# STM32_MCU.net
KiCad netlist of a schematic drawn in Altium Designer
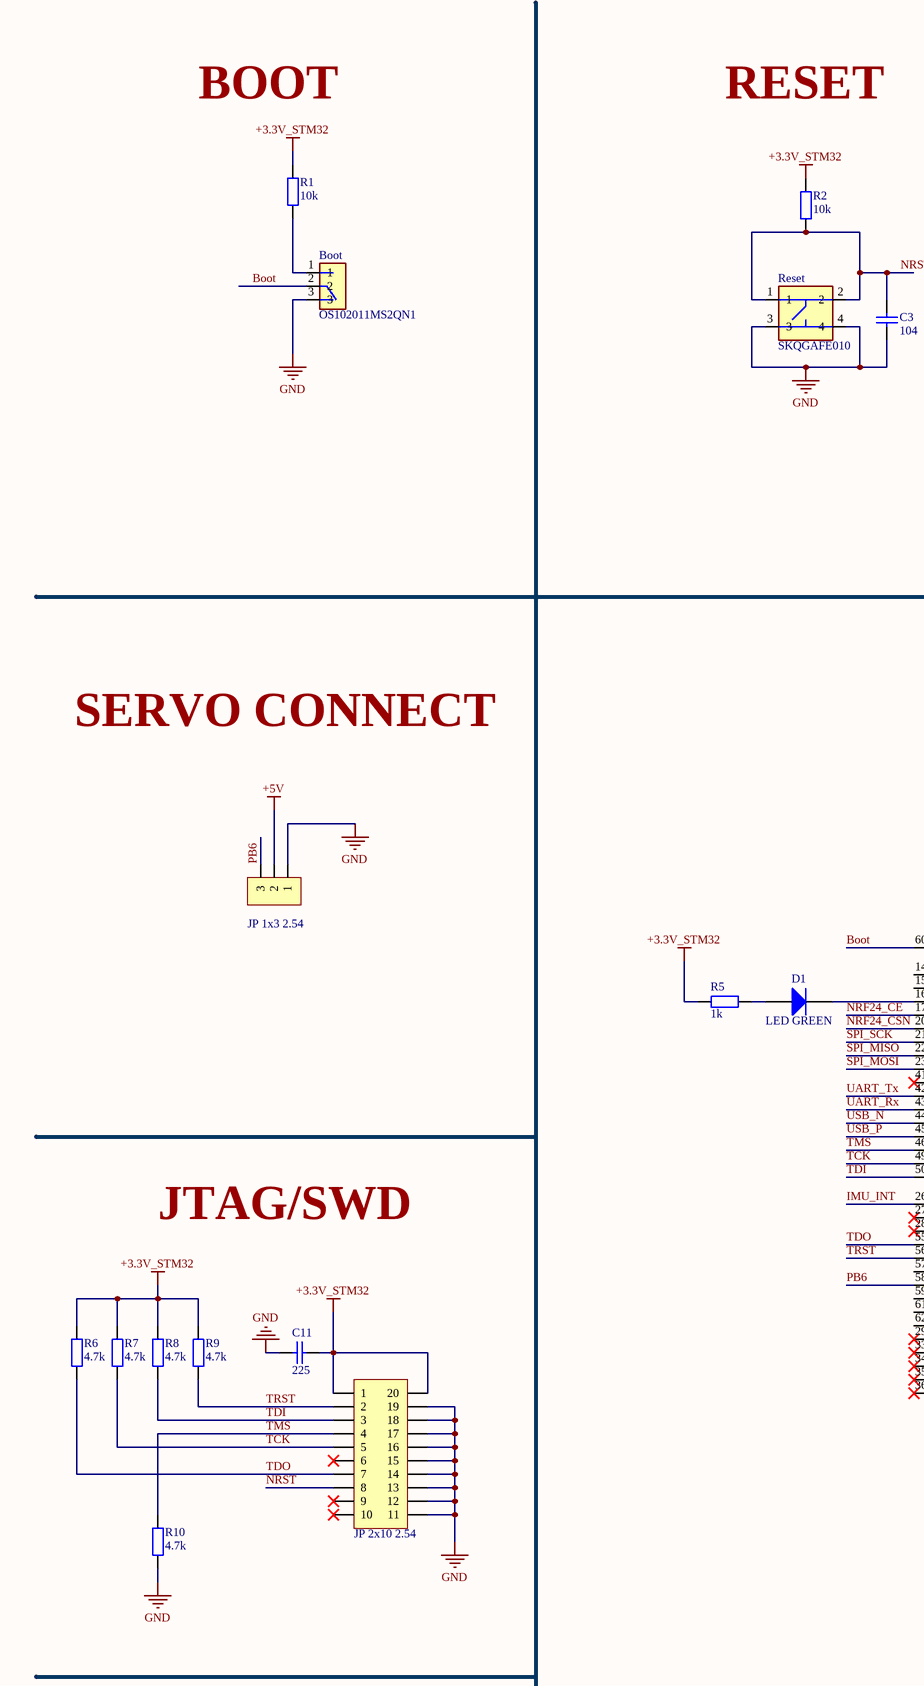
[diagram p0: STM32_MCU.SchDoc, left]
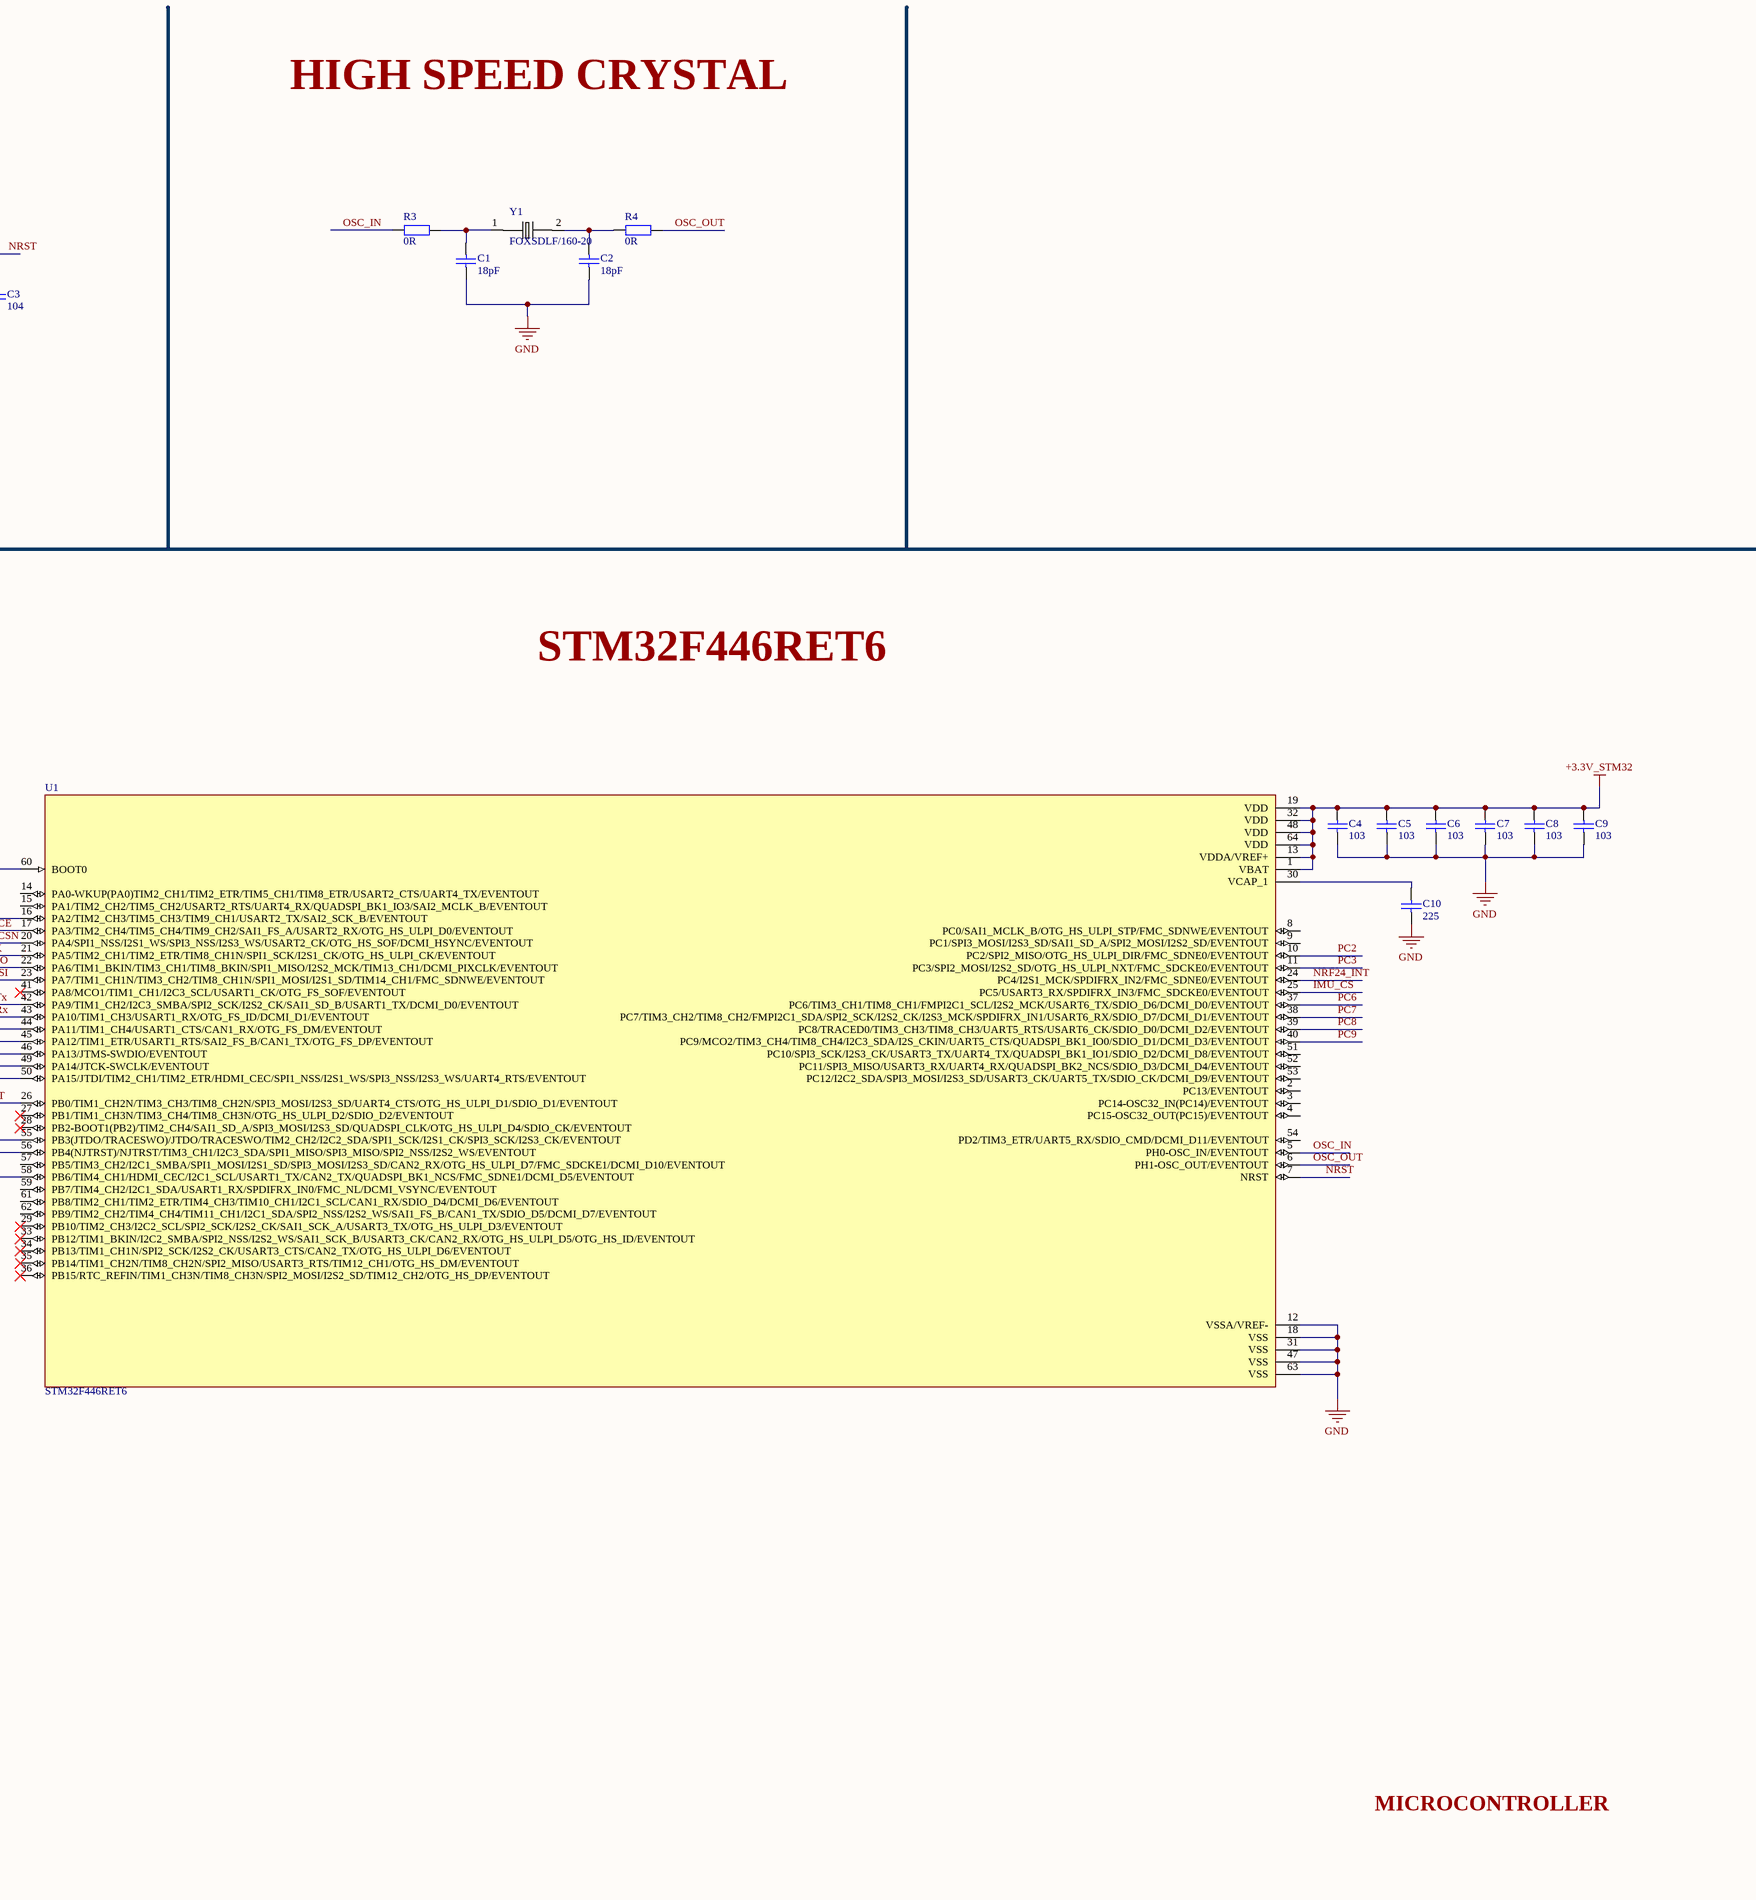
[diagram p1: STM32_MCU.SchDoc, right]

(export (version "E")
  (design (tool "Eeschema 10.0.6"))
  (components
    (comp (ref "Boot")
      (value "OS102011MS2QN1")
      (footprint "OS102011MS2QN1:SW_OS102011MS2QN1")
      (description "Switch Slide ON ON SPDT Top Slide 0.1A 12VDC 10000Cycles PC Pins Thru-Hole Bulk")
      (fields (field (name "MF") "{'manufacturer': u'C&K'}"))
      (libsource (lib "*") (part "OS102011MS2QN1"))
    )
    (comp (ref "C1")
      (value "18pF")
      (footprint "tu 0805")
      (description "Dán")
      (libsource (lib "Altium_Lib_by_KhueNguyenCreator") (part "Tu 0805 20pF 50V 10%"))
    )
    (comp (ref "C2")
      (value "18pF")
      (footprint "tu 0805")
      (description "Dán")
      (libsource (lib "Altium_Lib_by_KhueNguyenCreator") (part "Tu 0805 20pF 50V 10%"))
    )
    (comp (ref "C3")
      (value "104")
      (footprint "tu 1206")
      (description "Dán")
      (libsource (lib "Altium_Lib_by_KhueNguyenCreator") (part "Tu 1206 104 50V 20%"))
    )
    (comp (ref "C4")
      (value "103")
      (footprint "tu 0603")
      (description "Dán")
      (libsource (lib "Altium_Lib_by_KhueNguyenCreator") (part "Tu 0603 103 50V 10%"))
    )
    (comp (ref "C5")
      (value "103")
      (footprint "tu 0603")
      (description "Dán")
      (libsource (lib "Altium_Lib_by_KhueNguyenCreator") (part "Tu 0603 103 50V 10%"))
    )
    (comp (ref "C6")
      (value "103")
      (footprint "tu 0603")
      (description "Dán")
      (libsource (lib "Altium_Lib_by_KhueNguyenCreator") (part "Tu 0603 103 50V 10%"))
    )
    (comp (ref "C7")
      (value "103")
      (footprint "tu 0603")
      (description "Dán")
      (libsource (lib "Altium_Lib_by_KhueNguyenCreator") (part "Tu 0603 103 50V 10%"))
    )
    (comp (ref "C8")
      (value "103")
      (footprint "tu 0603")
      (description "Dán")
      (libsource (lib "Altium_Lib_by_KhueNguyenCreator") (part "Tu 0603 103 50V 10%"))
    )
    (comp (ref "C9")
      (value "103")
      (footprint "tu 0603")
      (description "Dán")
      (libsource (lib "Altium_Lib_by_KhueNguyenCreator") (part "Tu 0603 103 50V 10%"))
    )
    (comp (ref "C10")
      (value "225")
      (footprint "tu 0805")
      (description "Dán")
      (libsource (lib "Altium_Lib_by_KhueNguyenCreator") (part "Tu 0805 225 25V 10%"))
    )
    (comp (ref "C11")
      (value "225")
      (footprint "tu 0805")
      (description "Dán")
      (libsource (lib "Altium_Lib_by_KhueNguyenCreator") (part "Tu 0805 225 25V 10%"))
    )
    (comp (ref "D1")
      (value "LED GREEN")
      (footprint "J1-0603")
      (description "Default Diode")
      (fields (field (name "PUBLISHER") "Altium Limited"))
      (libsource (lib "MSP430_sch_1060821") (part "Diode"))
    )
    (comp (ref "R1")
      (value "10k")
      (footprint "tro smd 0603")
      (description "Dán")
      (libsource (lib "Altium_Lib_by_KhueNguyenCreator") (part "Tro 0603 1% 10k"))
    )
    (comp (ref "R2")
      (value "10k")
      (footprint "tro smd 0603")
      (description "Dán")
      (libsource (lib "Altium_Lib_by_KhueNguyenCreator") (part "Tro 0603 1% 10k"))
    )
    (comp (ref "R3")
      (value "0R")
      (footprint "tro smd 0603")
      (description "Dán")
      (libsource (lib "Altium_Lib_by_KhueNguyenCreator") (part "Tro 0603 1% 0R"))
    )
    (comp (ref "R4")
      (value "0R")
      (footprint "tro smd 0603")
      (description "Dán")
      (libsource (lib "Altium_Lib_by_KhueNguyenCreator") (part "Tro 0603 1% 0R"))
    )
    (comp (ref "R5")
      (value "1k")
      (footprint "tro smd 0603")
      (description "Dán")
      (libsource (lib "Altium_Lib_by_KhueNguyenCreator") (part "Tro 0603 1% 1k"))
    )
    (comp (ref "R6")
      (value "4.7k")
      (footprint "tro smd 0603")
      (description "Dán")
      (libsource (lib "Altium_Lib_by_KhueNguyenCreator") (part "Tro 0603 5% 4.7k"))
    )
    (comp (ref "R7")
      (value "4.7k")
      (footprint "tro smd 0603")
      (description "Dán")
      (libsource (lib "Altium_Lib_by_KhueNguyenCreator") (part "Tro 0603 5% 4.7k"))
    )
    (comp (ref "R8")
      (value "4.7k")
      (footprint "tro smd 0603")
      (description "Dán")
      (libsource (lib "Altium_Lib_by_KhueNguyenCreator") (part "Tro 0603 5% 4.7k"))
    )
    (comp (ref "R9")
      (value "4.7k")
      (footprint "tro smd 0603")
      (description "Dán")
      (libsource (lib "Altium_Lib_by_KhueNguyenCreator") (part "Tro 0603 5% 4.7k"))
    )
    (comp (ref "R10")
      (value "4.7k")
      (footprint "tro smd 0603")
      (description "Dán")
      (libsource (lib "Altium_Lib_by_KhueNguyenCreator") (part "Tro 0603 5% 4.7k"))
    )
    (comp (ref "Reset")
      (value "SKQGAFE010")
      (footprint "SW_SKQGAFE010")
      (description "Switch Tactile N.O. SPST Button Gull Wing 0.05A 12VDC 0.98N SMD T/R")
      (fields (field (name "MF") "{'manufacturer': u'ALPS'}"))
      (libsource (lib "SnapEDA_Library") (part "SKQGAFE010"))
    )
    (comp (ref "Servo")
      (value "JP 1x3 2.54")
      (footprint "JP 1x3 DT")
      (description "Cắm")
      (libsource (lib "Altium_Lib_by_KhueNguyenCreator") (part "JP 1x3 2.54 Duc Thang"))
    )
    (comp (ref "SWD/JTAG1")
      (value "JP 2x10 2.54")
      (footprint "JP 2x10 DT")
      (description "Cắm")
      (libsource (lib "Altium_Lib_by_KhueNguyenCreator") (part "JP 2x10 2.54 Duc Thang"))
    )
    (comp (ref "U1")
      (value "STM32F446RET6")
      (footprint "QFP50P1200X1200X160-64N")
      (description "MCU 32-Bit STM32 ARM Cortex M4 RISC 512KB Flash 2.5V/3.3V 64-Pin LQFP Tray")
      (fields (field (name "MF") "{'manufacturer': u'STMicroelectronics'}"))
      (libsource (lib "SnapEDA_Library") (part "STM32F446RET6"))
    )
    (comp (ref "Y1")
      (value "FOXSDLF/160-20")
      (footprint "SMD_Crystal")
      (description "Crystal 16MHz 20pF 2-Pin HC-49/SD")
      (fields (field (name "DIGI-KEY_PART_NUMBER") "631-1017-2-ND") (field (name "MF") "Fox"))
      (libsource (lib "MSP430_sch_1120816") (part "Crystal 16MHz 20pF 2-Pin"))
    )
  )
  (nets
    (net (code "1") (name "+3.3V_STM32") (class "Default")
      (node (ref "C11") (pin "1") (pinfunction "1_1") (pintype "passive"))
      (node (ref "C4") (pin "1") (pinfunction "1_1") (pintype "passive"))
      (node (ref "C5") (pin "1") (pinfunction "1_1") (pintype "passive"))
      (node (ref "C6") (pin "1") (pinfunction "1_1") (pintype "passive"))
      (node (ref "C7") (pin "1") (pinfunction "1_1") (pintype "passive"))
      (node (ref "C8") (pin "1") (pinfunction "1_1") (pintype "passive"))
      (node (ref "C9") (pin "1") (pinfunction "1_1") (pintype "passive"))
      (node (ref "R1") (pin "2") (pinfunction "2_2") (pintype "passive"))
      (node (ref "R2") (pin "2") (pinfunction "2_2") (pintype "passive"))
      (node (ref "R5") (pin "2") (pinfunction "2_2") (pintype "passive"))
      (node (ref "R6") (pin "2") (pinfunction "2_2") (pintype "passive"))
      (node (ref "R7") (pin "2") (pinfunction "2_2") (pintype "passive"))
      (node (ref "R8") (pin "2") (pinfunction "2_2") (pintype "passive"))
      (node (ref "R9") (pin "2") (pinfunction "2_2") (pintype "passive"))
      (node (ref "SWD/JTAG1") (pin "1") (pinfunction "1_1") (pintype "passive"))
      (node (ref "SWD/JTAG1") (pin "20") (pinfunction "20_20") (pintype "passive"))
      (node (ref "U1") (pin "1") (pinfunction "VBAT_1") (pintype "power_in"))
      (node (ref "U1") (pin "13") (pinfunction "VDDA/VREF+_13") (pintype "power_in"))
      (node (ref "U1") (pin "19") (pinfunction "VDD_19") (pintype "power_in"))
      (node (ref "U1") (pin "32") (pinfunction "VDD_32") (pintype "power_in"))
      (node (ref "U1") (pin "48") (pinfunction "VDD_48") (pintype "power_in"))
      (node (ref "U1") (pin "64") (pinfunction "VDD_64") (pintype "power_in"))
    )
    (net (code "2") (name "+5V") (class "Default")
      (node (ref "Servo") (pin "2") (pinfunction "2_2") (pintype "passive"))
    )
    (net (code "3") (name "/Boot") (class "Default")
      (node (ref "Boot") (pin "2") (pinfunction "2_2") (pintype "passive"))
      (node (ref "U1") (pin "60") (pinfunction "BOOT0_60") (pintype "input"))
    )
    (net (code "4") (name "/IMU_CS") (class "Default")
      (node (ref "U1") (pin "25") (pinfunction "PC5/USART3_RX/SPDIFRX_IN3/FMC_SDCKE0/EVENTOUT_25") (pintype "bidirectional"))
    )
    (net (code "5") (name "/IMU_INT") (class "Default")
      (node (ref "U1") (pin "26") (pinfunction "PB0/TIM1_CH2N/TIM3_CH3/TIM8_CH2N/SPI3_MOSI/I2S3_SD/UART4_CTS/OTG_HS_ULPI_D1/SDIO_D1/EVENTOUT_26") (pintype "bidirectional"))
    )
    (net (code "6") (name "/NRF24_CE") (class "Default")
      (node (ref "U1") (pin "17") (pinfunction "PA3/TIM2_CH4/TIM5_CH4/TIM9_CH2/SAI1_FS_A/USART2_RX/OTG_HS_ULPI_D0/EVENTOUT_17") (pintype "bidirectional"))
    )
    (net (code "7") (name "/NRF24_CSN") (class "Default")
      (node (ref "U1") (pin "20") (pinfunction "PA4/SPI1_NSS/I2S1_WS/SPI3_NSS/I2S3_WS/USART2_CK/OTG_HS_SOF/DCMI_HSYNC/EVENTOUT_20") (pintype "bidirectional"))
    )
    (net (code "8") (name "/NRF24_INT") (class "Default")
      (node (ref "U1") (pin "24") (pinfunction "PC4/I2S1_MCK/SPDIFRX_IN2/FMC_SDNE0/EVENTOUT_24") (pintype "bidirectional"))
    )
    (net (code "9") (name "/NRST") (class "Default")
      (node (ref "C3") (pin "1") (pinfunction "1_1") (pintype "passive"))
      (node (ref "R2") (pin "1") (pinfunction "1_1") (pintype "passive"))
      (node (ref "Reset") (pin "1") (pinfunction "1_1") (pintype "passive"))
      (node (ref "Reset") (pin "2") (pinfunction "2_2") (pintype "passive"))
      (node (ref "SWD/JTAG1") (pin "8") (pinfunction "8_8") (pintype "passive"))
      (node (ref "U1") (pin "7") (pinfunction "NRST_7") (pintype "bidirectional"))
    )
    (net (code "10") (name "/OSC_IN") (class "Default")
      (node (ref "R3") (pin "1") (pinfunction "1_1") (pintype "passive"))
      (node (ref "U1") (pin "5") (pinfunction "PH0-OSC_IN/EVENTOUT_5") (pintype "bidirectional"))
    )
    (net (code "11") (name "/OSC_OUT") (class "Default")
      (node (ref "R4") (pin "2") (pinfunction "2_2") (pintype "passive"))
      (node (ref "U1") (pin "6") (pinfunction "PH1-OSC_OUT/EVENTOUT_6") (pintype "bidirectional"))
    )
    (net (code "12") (name "/PB6") (class "Default")
      (node (ref "Servo") (pin "3") (pinfunction "3_3") (pintype "passive"))
      (node (ref "U1") (pin "58") (pinfunction "PB6/TIM4_CH1/HDMI_CEC/I2C1_SCL/USART1_TX/CAN2_TX/QUADSPI_BK1_NCS/FMC_SDNE1/DCMI_D5/EVENTOUT_58") (pintype "bidirectional"))
    )
    (net (code "13") (name "/PC2") (class "Default")
      (node (ref "U1") (pin "10") (pinfunction "PC2/SPI2_MISO/OTG_HS_ULPI_DIR/FMC_SDNE0/EVENTOUT_10") (pintype "bidirectional"))
    )
    (net (code "14") (name "/PC3") (class "Default")
      (node (ref "U1") (pin "11") (pinfunction "PC3/SPI2_MOSI/I2S2_SD/OTG_HS_ULPI_NXT/FMC_SDCKE0/EVENTOUT_11") (pintype "bidirectional"))
    )
    (net (code "15") (name "/PC6") (class "Default")
      (node (ref "U1") (pin "37") (pinfunction "PC6/TIM3_CH1/TIM8_CH1/FMPI2C1_SCL/I2S2_MCK/USART6_TX/SDIO_D6/DCMI_D0/EVENTOUT_37") (pintype "bidirectional"))
    )
    (net (code "16") (name "/PC7") (class "Default")
      (node (ref "U1") (pin "38") (pinfunction "PC7/TIM3_CH2/TIM8_CH2/FMPI2C1_SDA/SPI2_SCK/I2S2_CK/I2S3_MCK/SPDIFRX_IN1/USART6_RX/SDIO_D7/DCMI_D1/EVENTOUT_38") (pintype "bidirectional"))
    )
    (net (code "17") (name "/PC8") (class "Default")
      (node (ref "U1") (pin "39") (pinfunction "PC8/TRACED0/TIM3_CH3/TIM8_CH3/UART5_RTS/USART6_CK/SDIO_D0/DCMI_D2/EVENTOUT_39") (pintype "bidirectional"))
    )
    (net (code "18") (name "/PC9") (class "Default")
      (node (ref "U1") (pin "40") (pinfunction "PC9/MCO2/TIM3_CH4/TIM8_CH4/I2C3_SDA/I2S_CKIN/UART5_CTS/QUADSPI_BK1_IO0/SDIO_D1/DCMI_D3/EVENTOUT_40") (pintype "bidirectional"))
    )
    (net (code "19") (name "/SPI_MISO") (class "Default")
      (node (ref "U1") (pin "22") (pinfunction "PA6/TIM1_BKIN/TIM3_CH1/TIM8_BKIN/SPI1_MISO/I2S2_MCK/TIM13_CH1/DCMI_PIXCLK/EVENTOUT_22") (pintype "bidirectional"))
    )
    (net (code "20") (name "/SPI_MOSI") (class "Default")
      (node (ref "U1") (pin "23") (pinfunction "PA7/TIM1_CH1N/TIM3_CH2/TIM8_CH1N/SPI1_MOSI/I2S1_SD/TIM14_CH1/FMC_SDNWE/EVENTOUT_23") (pintype "bidirectional"))
    )
    (net (code "21") (name "/SPI_SCK") (class "Default")
      (node (ref "U1") (pin "21") (pinfunction "PA5/TIM2_CH1/TIM2_ETR/TIM8_CH1N/SPI1_SCK/I2S1_CK/OTG_HS_ULPI_CK/EVENTOUT_21") (pintype "bidirectional"))
    )
    (net (code "22") (name "/TCK") (class "Default")
      (node (ref "R7") (pin "1") (pinfunction "1_1") (pintype "passive"))
      (node (ref "SWD/JTAG1") (pin "5") (pinfunction "5_5") (pintype "passive"))
      (node (ref "U1") (pin "49") (pinfunction "PA14/JTCK-SWCLK/EVENTOUT_49") (pintype "bidirectional"))
    )
    (net (code "23") (name "/TDI") (class "Default")
      (node (ref "R8") (pin "1") (pinfunction "1_1") (pintype "passive"))
      (node (ref "SWD/JTAG1") (pin "3") (pinfunction "3_3") (pintype "passive"))
      (node (ref "U1") (pin "50") (pinfunction "PA15/JTDI/TIM2_CH1/TIM2_ETR/HDMI_CEC/SPI1_NSS/I2S1_WS/SPI3_NSS/I2S3_WS/UART4_RTS/EVENTOUT_50") (pintype "bidirectional"))
    )
    (net (code "24") (name "/TDO") (class "Default")
      (node (ref "R6") (pin "1") (pinfunction "1_1") (pintype "passive"))
      (node (ref "SWD/JTAG1") (pin "7") (pinfunction "7_7") (pintype "passive"))
      (node (ref "U1") (pin "55") (pinfunction "PB3(JTDO/TRACESWO)/JTDO/TRACESWO/TIM2_CH2/I2C2_SDA/SPI1_SCK/I2S1_CK/SPI3_SCK/I2S3_CK/EVENTOUT_55") (pintype "bidirectional"))
    )
    (net (code "25") (name "/TMS") (class "Default")
      (node (ref "R10") (pin "2") (pinfunction "2_2") (pintype "passive"))
      (node (ref "SWD/JTAG1") (pin "4") (pinfunction "4_4") (pintype "passive"))
      (node (ref "U1") (pin "46") (pinfunction "PA13/JTMS-SWDIO/EVENTOUT_46") (pintype "bidirectional"))
    )
    (net (code "26") (name "/TRST") (class "Default")
      (node (ref "R9") (pin "1") (pinfunction "1_1") (pintype "passive"))
      (node (ref "SWD/JTAG1") (pin "2") (pinfunction "2_2") (pintype "passive"))
      (node (ref "U1") (pin "56") (pinfunction "PB4(NJTRST)/NJTRST/TIM3_CH1/I2C3_SDA/SPI1_MISO/SPI3_MISO/SPI2_NSS/I2S2_WS/EVENTOUT_56") (pintype "bidirectional"))
    )
    (net (code "27") (name "/UART_Rx") (class "Default")
      (node (ref "U1") (pin "43") (pinfunction "PA10/TIM1_CH3/USART1_RX/OTG_FS_ID/DCMI_D1/EVENTOUT_43") (pintype "bidirectional"))
    )
    (net (code "28") (name "/UART_Tx") (class "Default")
      (node (ref "U1") (pin "42") (pinfunction "PA9/TIM1_CH2/I2C3_SMBA/SPI2_SCK/I2S2_CK/SAI1_SD_B/USART1_TX/DCMI_D0/EVENTOUT_42") (pintype "bidirectional"))
    )
    (net (code "29") (name "/USB_N") (class "Default")
      (node (ref "U1") (pin "44") (pinfunction "PA11/TIM1_CH4/USART1_CTS/CAN1_RX/OTG_FS_DM/EVENTOUT_44") (pintype "bidirectional"))
    )
    (net (code "30") (name "/USB_P") (class "Default")
      (node (ref "U1") (pin "45") (pinfunction "PA12/TIM1_ETR/USART1_RTS/SAI2_FS_B/CAN1_TX/OTG_FS_DP/EVENTOUT_45") (pintype "bidirectional"))
    )
    (net (code "31") (name "GND") (class "Default")
      (node (ref "Boot") (pin "3") (pinfunction "3_3") (pintype "passive"))
      (node (ref "C1") (pin "2") (pinfunction "2_2") (pintype "passive"))
      (node (ref "C10") (pin "2") (pinfunction "2_2") (pintype "passive"))
      (node (ref "C11") (pin "2") (pinfunction "2_2") (pintype "passive"))
      (node (ref "C2") (pin "2") (pinfunction "2_2") (pintype "passive"))
      (node (ref "C3") (pin "2") (pinfunction "2_2") (pintype "passive"))
      (node (ref "C4") (pin "2") (pinfunction "2_2") (pintype "passive"))
      (node (ref "C5") (pin "2") (pinfunction "2_2") (pintype "passive"))
      (node (ref "C6") (pin "2") (pinfunction "2_2") (pintype "passive"))
      (node (ref "C7") (pin "2") (pinfunction "2_2") (pintype "passive"))
      (node (ref "C8") (pin "2") (pinfunction "2_2") (pintype "passive"))
      (node (ref "C9") (pin "2") (pinfunction "2_2") (pintype "passive"))
      (node (ref "R10") (pin "1") (pinfunction "1_1") (pintype "passive"))
      (node (ref "Reset") (pin "3") (pinfunction "3_3") (pintype "passive"))
      (node (ref "Reset") (pin "4") (pinfunction "4_4") (pintype "passive"))
      (node (ref "SWD/JTAG1") (pin "11") (pinfunction "11_11") (pintype "passive"))
      (node (ref "SWD/JTAG1") (pin "12") (pinfunction "12_12") (pintype "passive"))
      (node (ref "SWD/JTAG1") (pin "13") (pinfunction "13_13") (pintype "passive"))
      (node (ref "SWD/JTAG1") (pin "14") (pinfunction "14_14") (pintype "passive"))
      (node (ref "SWD/JTAG1") (pin "15") (pinfunction "15_15") (pintype "passive"))
      (node (ref "SWD/JTAG1") (pin "16") (pinfunction "16_16") (pintype "passive"))
      (node (ref "SWD/JTAG1") (pin "17") (pinfunction "17_17") (pintype "passive"))
      (node (ref "SWD/JTAG1") (pin "18") (pinfunction "18_18") (pintype "passive"))
      (node (ref "SWD/JTAG1") (pin "19") (pinfunction "19_19") (pintype "passive"))
      (node (ref "Servo") (pin "1") (pinfunction "1_1") (pintype "passive"))
      (node (ref "U1") (pin "12") (pinfunction "VSSA/VREF-_12") (pintype "power_in"))
      (node (ref "U1") (pin "18") (pinfunction "VSS_18") (pintype "power_in"))
      (node (ref "U1") (pin "31") (pinfunction "VSS_31") (pintype "power_in"))
      (node (ref "U1") (pin "47") (pinfunction "VSS_47") (pintype "power_in"))
      (node (ref "U1") (pin "63") (pinfunction "VSS_63") (pintype "power_in"))
    )
    (net (code "32") (name "Net-(Boot-Pad1)") (class "Default")
      (node (ref "Boot") (pin "1") (pinfunction "1_1") (pintype "passive"))
      (node (ref "R1") (pin "1") (pinfunction "1_1") (pintype "passive"))
    )
    (net (code "33") (name "Net-(C1-Pad1)") (class "Default")
      (node (ref "C1") (pin "1") (pinfunction "1_1") (pintype "passive"))
      (node (ref "R3") (pin "2") (pinfunction "2_2") (pintype "passive"))
      (node (ref "Y1") (pin "1") (pinfunction "1_1") (pintype "passive"))
    )
    (net (code "34") (name "Net-(C2-Pad1)") (class "Default")
      (node (ref "C2") (pin "1") (pinfunction "1_1") (pintype "passive"))
      (node (ref "R4") (pin "1") (pinfunction "1_1") (pintype "passive"))
      (node (ref "Y1") (pin "2") (pinfunction "2_2") (pintype "passive"))
    )
    (net (code "35") (name "Net-(D1-A)") (class "Default")
      (node (ref "D1") (pin "1") (pinfunction "A_1") (pintype "passive"))
      (node (ref "R5") (pin "1") (pinfunction "1_1") (pintype "passive"))
    )
    (net (code "36") (name "Net-(D1-K)") (class "Default")
      (node (ref "D1") (pin "2") (pinfunction "K_2") (pintype "passive"))
      (node (ref "U1") (pin "16") (pinfunction "PA2/TIM2_CH3/TIM5_CH3/TIM9_CH1/USART2_TX/SAI2_SCK_B/EVENTOUT_16") (pintype "bidirectional"))
    )
    (net (code "37") (name "Net-(U1-VCAP_1)") (class "Default")
      (node (ref "C10") (pin "1") (pinfunction "1_1") (pintype "passive"))
      (node (ref "U1") (pin "30") (pinfunction "VCAP_1_30") (pintype "power_in"))
    )
    (net (code "38") (name "unconnected-(SWD/JTAG1-Pad6)") (class "Default")
      (node (ref "SWD/JTAG1") (pin "6") (pinfunction "6_6") (pintype "passive+no_connect"))
    )
    (net (code "39") (name "unconnected-(SWD/JTAG1-Pad9)") (class "Default")
      (node (ref "SWD/JTAG1") (pin "9") (pinfunction "9_9") (pintype "passive+no_connect"))
    )
    (net (code "40") (name "unconnected-(SWD/JTAG1-Pad10)") (class "Default")
      (node (ref "SWD/JTAG1") (pin "10") (pinfunction "10_10") (pintype "passive+no_connect"))
    )
    (net (code "41") (name "unconnected-(U1-PA0-WKUP(PA0)TIM2_CH1{slash}TIM2_ETR{slash}TIM5_CH1{slash}TIM8_ETR{slash}USART2_CTS{slash}UART4_TX{slash}EVENTOUT-Pad14)") (class "Default")
      (node (ref "U1") (pin "14") (pinfunction "PA0-WKUP(PA0)TIM2_CH1/TIM2_ETR/TIM5_CH1/TIM8_ETR/USART2_CTS/UART4_TX/EVENTOUT_14") (pintype "bidirectional"))
    )
    (net (code "42") (name "unconnected-(U1-PA1{slash}TIM2_CH2{slash}TIM5_CH2{slash}USART2_RTS{slash}UART4_RX{slash}QUADSPI_BK1_IO3{slash}SAI2_MCLK_B{slash}EVENTOUT-Pad15)") (class "Default")
      (node (ref "U1") (pin "15") (pinfunction "PA1/TIM2_CH2/TIM5_CH2/USART2_RTS/UART4_RX/QUADSPI_BK1_IO3/SAI2_MCLK_B/EVENTOUT_15") (pintype "bidirectional"))
    )
    (net (code "43") (name "unconnected-(U1-PA8{slash}MCO1{slash}TIM1_CH1{slash}I2C3_SCL{slash}USART1_CK{slash}OTG_FS_SOF{slash}EVENTOUT-Pad41)") (class "Default")
      (node (ref "U1") (pin "41") (pinfunction "PA8/MCO1/TIM1_CH1/I2C3_SCL/USART1_CK/OTG_FS_SOF/EVENTOUT_41") (pintype "bidirectional+no_connect"))
    )
    (net (code "44") (name "unconnected-(U1-PB1{slash}TIM1_CH3N{slash}TIM3_CH4{slash}TIM8_CH3N{slash}OTG_HS_ULPI_D2{slash}SDIO_D2{slash}EVENTOUT-Pad27)") (class "Default")
      (node (ref "U1") (pin "27") (pinfunction "PB1/TIM1_CH3N/TIM3_CH4/TIM8_CH3N/OTG_HS_ULPI_D2/SDIO_D2/EVENTOUT_27") (pintype "bidirectional+no_connect"))
    )
    (net (code "45") (name "unconnected-(U1-PB2-BOOT1(PB2){slash}TIM2_CH4{slash}SAI1_SD_A{slash}SPI3_MOSI{slash}I2S3_SD{slash}QUADSPI_CLK{slash}OTG_HS_ULPI_D4{slash}SDIO_CK{slash}EVENTOUT-Pad28)") (class "Default")
      (node (ref "U1") (pin "28") (pinfunction "PB2-BOOT1(PB2)/TIM2_CH4/SAI1_SD_A/SPI3_MOSI/I2S3_SD/QUADSPI_CLK/OTG_HS_ULPI_D4/SDIO_CK/EVENTOUT_28") (pintype "bidirectional+no_connect"))
    )
    (net (code "46") (name "unconnected-(U1-PB5{slash}TIM3_CH2{slash}I2C1_SMBA{slash}SPI1_MOSI{slash}I2S1_SD{slash}SPI3_MOSI{slash}I2S3_SD{slash}CAN2_RX{slash}OTG_HS_ULPI_D7{slash}FMC_SDCKE1{slash}DCMI_D10{slash}EVENTOUT-Pad57)") (class "Default")
      (node (ref "U1") (pin "57") (pinfunction "PB5/TIM3_CH2/I2C1_SMBA/SPI1_MOSI/I2S1_SD/SPI3_MOSI/I2S3_SD/CAN2_RX/OTG_HS_ULPI_D7/FMC_SDCKE1/DCMI_D10/EVENTOUT_57") (pintype "bidirectional"))
    )
    (net (code "47") (name "unconnected-(U1-PB7{slash}TIM4_CH2{slash}I2C1_SDA{slash}USART1_RX{slash}SPDIFRX_IN0{slash}FMC_NL{slash}DCMI_VSYNC{slash}EVENTOUT-Pad59)") (class "Default")
      (node (ref "U1") (pin "59") (pinfunction "PB7/TIM4_CH2/I2C1_SDA/USART1_RX/SPDIFRX_IN0/FMC_NL/DCMI_VSYNC/EVENTOUT_59") (pintype "bidirectional"))
    )
    (net (code "48") (name "unconnected-(U1-PB8{slash}TIM2_CH1{slash}TIM2_ETR{slash}TIM4_CH3{slash}TIM10_CH1{slash}I2C1_SCL{slash}CAN1_RX{slash}SDIO_D4{slash}DCMI_D6{slash}EVENTOUT-Pad61)") (class "Default")
      (node (ref "U1") (pin "61") (pinfunction "PB8/TIM2_CH1/TIM2_ETR/TIM4_CH3/TIM10_CH1/I2C1_SCL/CAN1_RX/SDIO_D4/DCMI_D6/EVENTOUT_61") (pintype "bidirectional"))
    )
    (net (code "49") (name "unconnected-(U1-PB9{slash}TIM2_CH2{slash}TIM4_CH4{slash}TIM11_CH1{slash}I2C1_SDA{slash}SPI2_NSS{slash}I2S2_WS{slash}SAI1_FS_B{slash}CAN1_TX{slash}SDIO_D5{slash}DCMI_D7{slash}EVENTOUT-Pad62)") (class "Default")
      (node (ref "U1") (pin "62") (pinfunction "PB9/TIM2_CH2/TIM4_CH4/TIM11_CH1/I2C1_SDA/SPI2_NSS/I2S2_WS/SAI1_FS_B/CAN1_TX/SDIO_D5/DCMI_D7/EVENTOUT_62") (pintype "bidirectional"))
    )
    (net (code "50") (name "unconnected-(U1-PB10{slash}TIM2_CH3{slash}I2C2_SCL{slash}SPI2_SCK{slash}I2S2_CK{slash}SAI1_SCK_A{slash}USART3_TX{slash}OTG_HS_ULPI_D3{slash}EVENTOUT-Pad29)") (class "Default")
      (node (ref "U1") (pin "29") (pinfunction "PB10/TIM2_CH3/I2C2_SCL/SPI2_SCK/I2S2_CK/SAI1_SCK_A/USART3_TX/OTG_HS_ULPI_D3/EVENTOUT_29") (pintype "bidirectional+no_connect"))
    )
    (net (code "51") (name "unconnected-(U1-PB12{slash}TIM1_BKIN{slash}I2C2_SMBA{slash}SPI2_NSS{slash}I2S2_WS{slash}SAI1_SCK_B{slash}USART3_CK{slash}CAN2_RX{slash}OTG_HS_ULPI_D5{slash}OTG_HS_ID{slash}EVENTOUT-Pad33)") (class "Default")
      (node (ref "U1") (pin "33") (pinfunction "PB12/TIM1_BKIN/I2C2_SMBA/SPI2_NSS/I2S2_WS/SAI1_SCK_B/USART3_CK/CAN2_RX/OTG_HS_ULPI_D5/OTG_HS_ID/EVENTOUT_33") (pintype "bidirectional+no_connect"))
    )
    (net (code "52") (name "unconnected-(U1-PB13{slash}TIM1_CH1N{slash}SPI2_SCK{slash}I2S2_CK{slash}USART3_CTS{slash}CAN2_TX{slash}OTG_HS_ULPI_D6{slash}EVENTOUT-Pad34)") (class "Default")
      (node (ref "U1") (pin "34") (pinfunction "PB13/TIM1_CH1N/SPI2_SCK/I2S2_CK/USART3_CTS/CAN2_TX/OTG_HS_ULPI_D6/EVENTOUT_34") (pintype "bidirectional+no_connect"))
    )
    (net (code "53") (name "unconnected-(U1-PB14{slash}TIM1_CH2N{slash}TIM8_CH2N{slash}SPI2_MISO{slash}USART3_RTS{slash}TIM12_CH1{slash}OTG_HS_DM{slash}EVENTOUT-Pad35)") (class "Default")
      (node (ref "U1") (pin "35") (pinfunction "PB14/TIM1_CH2N/TIM8_CH2N/SPI2_MISO/USART3_RTS/TIM12_CH1/OTG_HS_DM/EVENTOUT_35") (pintype "bidirectional+no_connect"))
    )
    (net (code "54") (name "unconnected-(U1-PB15{slash}RTC_REFIN{slash}TIM1_CH3N{slash}TIM8_CH3N{slash}SPI2_MOSI{slash}I2S2_SD{slash}TIM12_CH2{slash}OTG_HS_DP{slash}EVENTOUT-Pad36)") (class "Default")
      (node (ref "U1") (pin "36") (pinfunction "PB15/RTC_REFIN/TIM1_CH3N/TIM8_CH3N/SPI2_MOSI/I2S2_SD/TIM12_CH2/OTG_HS_DP/EVENTOUT_36") (pintype "bidirectional+no_connect"))
    )
    (net (code "55") (name "unconnected-(U1-PC0{slash}SAI1_MCLK_B{slash}OTG_HS_ULPI_STP{slash}FMC_SDNWE{slash}EVENTOUT-Pad8)") (class "Default")
      (node (ref "U1") (pin "8") (pinfunction "PC0/SAI1_MCLK_B/OTG_HS_ULPI_STP/FMC_SDNWE/EVENTOUT_8") (pintype "bidirectional"))
    )
    (net (code "56") (name "unconnected-(U1-PC1{slash}SPI3_MOSI{slash}I2S3_SD{slash}SAI1_SD_A{slash}SPI2_MOSI{slash}I2S2_SD{slash}EVENTOUT-Pad9)") (class "Default")
      (node (ref "U1") (pin "9") (pinfunction "PC1/SPI3_MOSI/I2S3_SD/SAI1_SD_A/SPI2_MOSI/I2S2_SD/EVENTOUT_9") (pintype "bidirectional"))
    )
    (net (code "57") (name "unconnected-(U1-PC10{slash}SPI3_SCK{slash}I2S3_CK{slash}USART3_TX{slash}UART4_TX{slash}QUADSPI_BK1_IO1{slash}SDIO_D2{slash}DCMI_D8{slash}EVENTOUT-Pad51)") (class "Default")
      (node (ref "U1") (pin "51") (pinfunction "PC10/SPI3_SCK/I2S3_CK/USART3_TX/UART4_TX/QUADSPI_BK1_IO1/SDIO_D2/DCMI_D8/EVENTOUT_51") (pintype "bidirectional"))
    )
    (net (code "58") (name "unconnected-(U1-PC11{slash}SPI3_MISO{slash}USART3_RX{slash}UART4_RX{slash}QUADSPI_BK2_NCS{slash}SDIO_D3{slash}DCMI_D4{slash}EVENTOUT-Pad52)") (class "Default")
      (node (ref "U1") (pin "52") (pinfunction "PC11/SPI3_MISO/USART3_RX/UART4_RX/QUADSPI_BK2_NCS/SDIO_D3/DCMI_D4/EVENTOUT_52") (pintype "bidirectional"))
    )
    (net (code "59") (name "unconnected-(U1-PC12{slash}I2C2_SDA{slash}SPI3_MOSI{slash}I2S3_SD{slash}USART3_CK{slash}UART5_TX{slash}SDIO_CK{slash}DCMI_D9{slash}EVENTOUT-Pad53)") (class "Default")
      (node (ref "U1") (pin "53") (pinfunction "PC12/I2C2_SDA/SPI3_MOSI/I2S3_SD/USART3_CK/UART5_TX/SDIO_CK/DCMI_D9/EVENTOUT_53") (pintype "bidirectional"))
    )
    (net (code "60") (name "unconnected-(U1-PC13{slash}EVENTOUT-Pad2)") (class "Default")
      (node (ref "U1") (pin "2") (pinfunction "PC13/EVENTOUT_2") (pintype "bidirectional"))
    )
    (net (code "61") (name "unconnected-(U1-PC14-OSC32_IN(PC14){slash}EVENTOUT-Pad3)") (class "Default")
      (node (ref "U1") (pin "3") (pinfunction "PC14-OSC32_IN(PC14)/EVENTOUT_3") (pintype "bidirectional"))
    )
    (net (code "62") (name "unconnected-(U1-PC15-OSC32_OUT(PC15){slash}EVENTOUT-Pad4)") (class "Default")
      (node (ref "U1") (pin "4") (pinfunction "PC15-OSC32_OUT(PC15)/EVENTOUT_4") (pintype "bidirectional"))
    )
    (net (code "63") (name "unconnected-(U1-PD2{slash}TIM3_ETR{slash}UART5_RX{slash}SDIO_CMD{slash}DCMI_D11{slash}EVENTOUT-Pad54)") (class "Default")
      (node (ref "U1") (pin "54") (pinfunction "PD2/TIM3_ETR/UART5_RX/SDIO_CMD/DCMI_D11/EVENTOUT_54") (pintype "bidirectional"))
    )
  )
)
